# dallamcseng.net
KiCad netlist of a schematic drawn in EAGLE
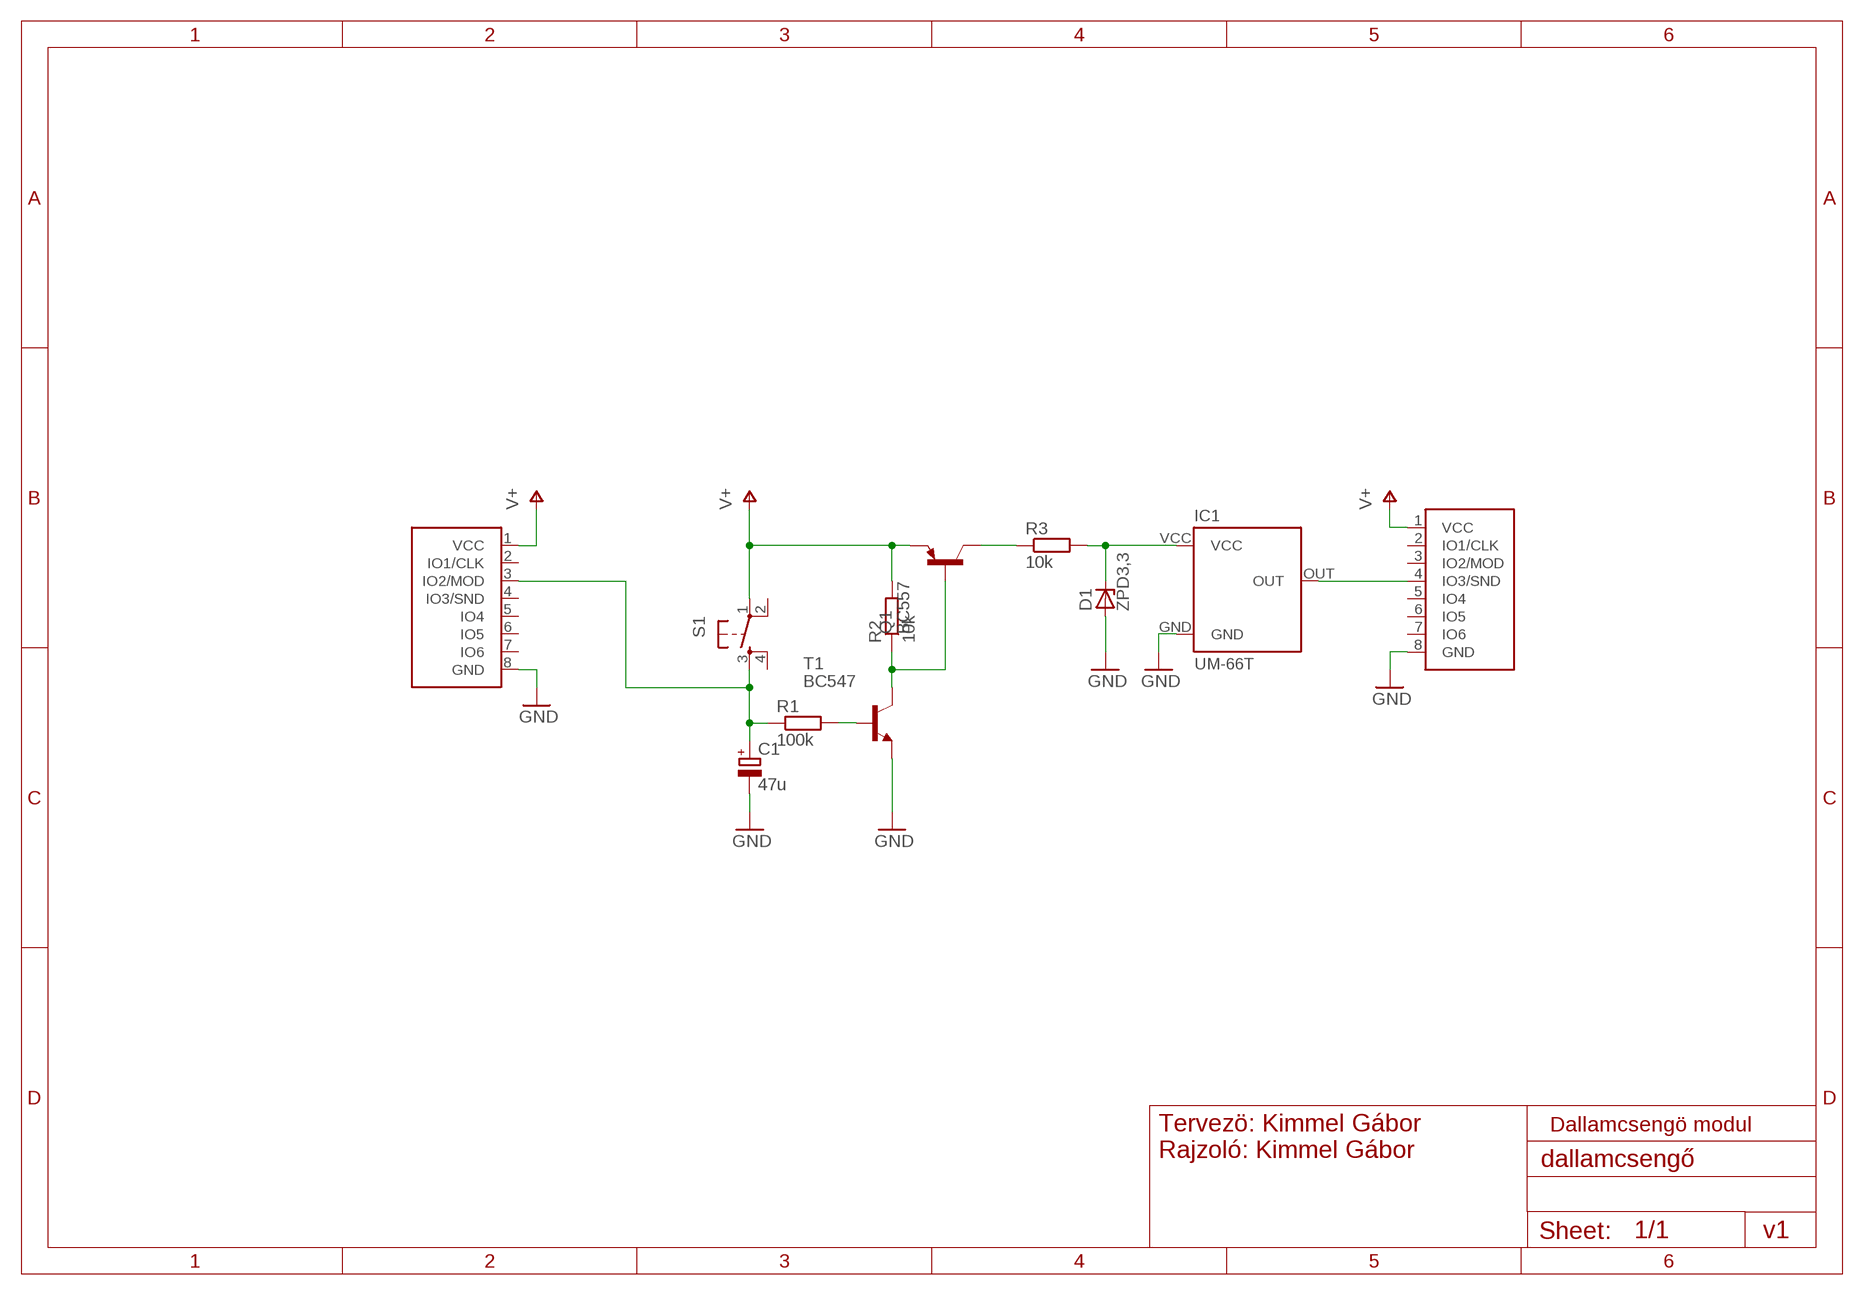
[diagram p0: schematic, sheet 1]

(export (version "E")
  (design (tool "Eeschema 10.0.6"))
  (components
    (comp (ref "C1")
      (value "47u")
      (footprint "eagle-import:E5-8,5")
      (libsource (lib "eagle-import") (part "CPOL-EUE5-8.5"))
    )
    (comp (ref "D1")
      (value "ZPD3,3")
      (footprint "eagle-import:DO35Z10")
      (libsource (lib "eagle-import") (part "ZENER-DIODEDO35Z10"))
    )
    (comp (ref "IC1")
      (value "UM-66T")
      (footprint "eagle-import:TO92-DCS")
      (libsource (lib "eagle-import") (part "UM-66T"))
    )
    (comp (ref "Q1")
      (value "BC557")
      (footprint "eagle-import:TO92")
      (libsource (lib "eagle-import") (part "BC557"))
    )
    (comp (ref "R1")
      (value "100k")
      (footprint "eagle-import:0309_12")
      (libsource (lib "eagle-import") (part "R-EU_0309/12"))
    )
    (comp (ref "R2")
      (value "10k")
      (footprint "eagle-import:0309_12")
      (libsource (lib "eagle-import") (part "R-EU_0309/12"))
    )
    (comp (ref "R3")
      (value "10k")
      (footprint "eagle-import:0309_12")
      (libsource (lib "eagle-import") (part "R-EU_0309/12"))
    )
    (comp (ref "S1")
      (value "TAC_SWITCHPTH")
      (footprint "eagle-import:TACTILE-PTH")
      (libsource (lib "eagle-import") (part "TAC_SWITCHPTH"))
    )
    (comp (ref "T1")
      (value "BC547")
      (footprint "eagle-import:TO92")
      (libsource (lib "eagle-import") (part "BC547"))
    )
    (comp (ref "U$1")
      (value "GANZ-CONNECTOR")
      (footprint "eagle-import:FE08W")
      (libsource (lib "eagle-import") (part "GANZ-CONNECTOR"))
    )
    (comp (ref "U$2")
      (value "GANZ-CONNECTOR-OUT")
      (footprint "eagle-import:MA08-1W")
      (libsource (lib "eagle-import") (part "GANZ-CONNECTOR-OUT"))
    )
  )
  (nets
    (net (code "1") (name "GND") (class "Default")
      (node (ref "C1") (pin "-") (pinfunction "-_-") (pintype "passive"))
      (node (ref "D1") (pin "A") (pinfunction "A_A") (pintype "passive"))
      (node (ref "IC1") (pin "GND") (pinfunction "GND_GND") (pintype "power_in"))
      (node (ref "T1") (pin "1") (pinfunction "E_1") (pintype "passive"))
      (node (ref "U$1") (pin "8") (pinfunction "GND_8") (pintype "bidirectional"))
      (node (ref "U$2") (pin "8") (pinfunction "GND_8") (pintype "bidirectional"))
    )
    (net (code "2") (name "Net-(D1-PadC)") (class "Default")
      (node (ref "D1") (pin "C") (pinfunction "C_C") (pintype "passive"))
      (node (ref "IC1") (pin "VCC") (pinfunction "VCC_VCC") (pintype "power_in"))
      (node (ref "R3") (pin "2") (pinfunction "2_2") (pintype "passive"))
    )
    (net (code "3") (name "Net-(Q1-B)") (class "Default")
      (node (ref "Q1") (pin "2") (pinfunction "B_2") (pintype "passive"))
      (node (ref "R2") (pin "1") (pinfunction "1_1") (pintype "passive"))
      (node (ref "T1") (pin "3") (pinfunction "C_3") (pintype "passive"))
    )
    (net (code "4") (name "Net-(Q1-C)") (class "Default")
      (node (ref "Q1") (pin "3") (pinfunction "C_3") (pintype "passive"))
      (node (ref "R3") (pin "1") (pinfunction "1_1") (pintype "passive"))
    )
    (net (code "5") (name "Net-(T1-B)") (class "Default")
      (node (ref "R1") (pin "2") (pinfunction "2_2") (pintype "passive"))
      (node (ref "T1") (pin "2") (pinfunction "B_2") (pintype "passive"))
    )
    (net (code "6") (name "Net-(U$1-IO2{slash}MOD)") (class "Default")
      (node (ref "C1") (pin "+") (pinfunction "+_+") (pintype "passive"))
      (node (ref "R1") (pin "1") (pinfunction "1_1") (pintype "passive"))
      (node (ref "S1") (pin "3") (pinfunction "3_3") (pintype "passive"))
      (node (ref "U$1") (pin "3") (pinfunction "IO2/MOD_3") (pintype "bidirectional"))
    )
    (net (code "7") (name "Net-(U$2-IO3{slash}SND)") (class "Default")
      (node (ref "IC1") (pin "OUT") (pinfunction "OUT_OUT") (pintype "output"))
      (node (ref "U$2") (pin "4") (pinfunction "IO3/SND_4") (pintype "bidirectional"))
    )
    (net (code "8") (name "V+") (class "Default")
      (node (ref "Q1") (pin "1") (pinfunction "E_1") (pintype "passive"))
      (node (ref "R2") (pin "2") (pinfunction "2_2") (pintype "passive"))
      (node (ref "S1") (pin "1") (pinfunction "1_1") (pintype "passive"))
      (node (ref "U$1") (pin "1") (pinfunction "VCC_1") (pintype "bidirectional"))
      (node (ref "U$2") (pin "1") (pinfunction "VCC_1") (pintype "bidirectional"))
    )
    (net (code "9") (name "unconnected-(S1-Pad2)") (class "Default")
      (node (ref "S1") (pin "2") (pinfunction "2_2") (pintype "passive"))
    )
    (net (code "10") (name "unconnected-(S1-Pad4)") (class "Default")
      (node (ref "S1") (pin "4") (pinfunction "4_4") (pintype "passive"))
    )
    (net (code "11") (name "unconnected-(U$1-IO1{slash}CLK-Pad2)") (class "Default")
      (node (ref "U$1") (pin "2") (pinfunction "IO1/CLK_2") (pintype "bidirectional"))
    )
    (net (code "12") (name "unconnected-(U$1-IO3{slash}SND-Pad4)") (class "Default")
      (node (ref "U$1") (pin "4") (pinfunction "IO3/SND_4") (pintype "bidirectional"))
    )
    (net (code "13") (name "unconnected-(U$1-IO4-Pad5)") (class "Default")
      (node (ref "U$1") (pin "5") (pinfunction "IO4_5") (pintype "bidirectional"))
    )
    (net (code "14") (name "unconnected-(U$1-IO5-Pad6)") (class "Default")
      (node (ref "U$1") (pin "6") (pinfunction "IO5_6") (pintype "bidirectional"))
    )
    (net (code "15") (name "unconnected-(U$1-IO6-Pad7)") (class "Default")
      (node (ref "U$1") (pin "7") (pinfunction "IO6_7") (pintype "bidirectional"))
    )
    (net (code "16") (name "unconnected-(U$2-IO1{slash}CLK-Pad2)") (class "Default")
      (node (ref "U$2") (pin "2") (pinfunction "IO1/CLK_2") (pintype "bidirectional"))
    )
    (net (code "17") (name "unconnected-(U$2-IO2{slash}MOD-Pad3)") (class "Default")
      (node (ref "U$2") (pin "3") (pinfunction "IO2/MOD_3") (pintype "bidirectional"))
    )
    (net (code "18") (name "unconnected-(U$2-IO4-Pad5)") (class "Default")
      (node (ref "U$2") (pin "5") (pinfunction "IO4_5") (pintype "bidirectional"))
    )
    (net (code "19") (name "unconnected-(U$2-IO5-Pad6)") (class "Default")
      (node (ref "U$2") (pin "6") (pinfunction "IO5_6") (pintype "bidirectional"))
    )
    (net (code "20") (name "unconnected-(U$2-IO6-Pad7)") (class "Default")
      (node (ref "U$2") (pin "7") (pinfunction "IO6_7") (pintype "bidirectional"))
    )
  )
)
